# display.net
KiCad netlist of a schematic drawn in EAGLE
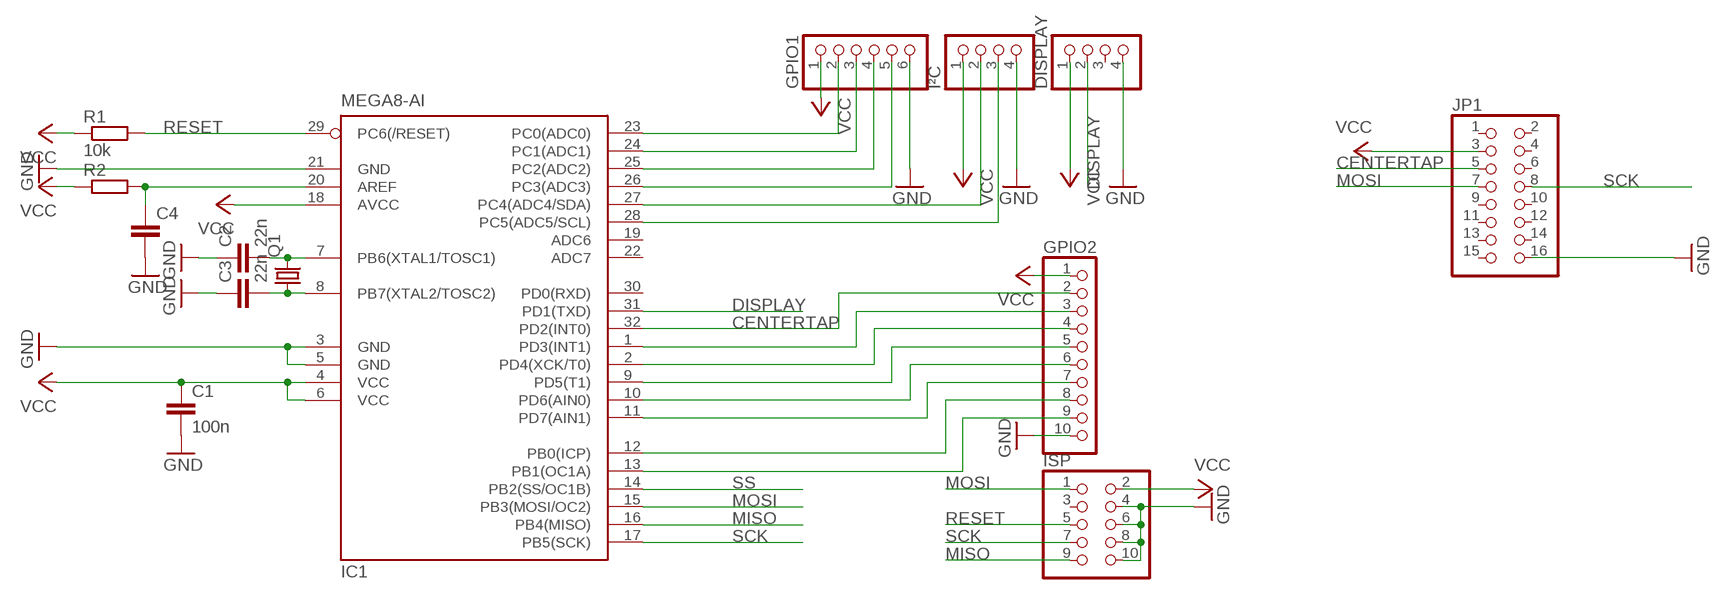
[diagram p0: schematic, sheet 1]

(export (version "E")
  (design (tool "Eeschema 10.0.6"))
  (components
    (comp (ref "C1")
      (value "100n")
      (footprint "eagle-import:C0805")
      (libsource (lib "eagle-import") (part "C-EUC0805"))
    )
    (comp (ref "C2")
      (value "22n")
      (footprint "eagle-import:C0805")
      (libsource (lib "eagle-import") (part "C-EUC0805"))
    )
    (comp (ref "C3")
      (value "22n")
      (footprint "eagle-import:C0805")
      (libsource (lib "eagle-import") (part "C-EUC0805"))
    )
    (comp (ref "C4")
      (value "C-EUC0805")
      (footprint "eagle-import:C0805")
      (libsource (lib "eagle-import") (part "C-EUC0805"))
    )
    (comp (ref "DISPLAY")
      (value "PINHD-1X4")
      (footprint "eagle-import:1X04")
      (libsource (lib "eagle-import") (part "PINHD-1X4"))
    )
    (comp (ref "GPIO1")
      (value "PINHD-1X6")
      (footprint "eagle-import:1X06")
      (libsource (lib "eagle-import") (part "PINHD-1X6"))
    )
    (comp (ref "GPIO2")
      (value "PINHD-1X10")
      (footprint "eagle-import:1X10")
      (libsource (lib "eagle-import") (part "PINHD-1X10"))
    )
    (comp (ref "IC1")
      (value "MEGA8-AI")
      (footprint "eagle-import:TQFP32-08")
      (fields (field (name "MPN") "ATMEGA8-16AU"))
      (libsource (lib "eagle-import") (part "MEGA8-AI"))
    )
    (comp (ref "ISP")
      (value "PINHD-2X5")
      (footprint "eagle-import:2X05")
      (libsource (lib "eagle-import") (part "PINHD-2X5"))
    )
    (comp (ref "I²C")
      (value "PINHD-1X4")
      (footprint "eagle-import:1X04")
      (libsource (lib "eagle-import") (part "PINHD-1X4"))
    )
    (comp (ref "JP1")
      (value "PINHD-2X8")
      (footprint "eagle-import:2X08")
      (libsource (lib "eagle-import") (part "PINHD-2X8"))
    )
    (comp (ref "Q1")
      (value "CRYSTALSM49")
      (footprint "eagle-import:SM49")
      (libsource (lib "eagle-import") (part "CRYSTALSM49"))
    )
    (comp (ref "R1")
      (value "10k")
      (footprint "eagle-import:R0805")
      (libsource (lib "eagle-import") (part "R-EU_R0805"))
    )
    (comp (ref "R2")
      (value "R-EU_R0805")
      (footprint "eagle-import:R0805")
      (libsource (lib "eagle-import") (part "R-EU_R0805"))
    )
  )
  (nets
    (net (code "1") (name "/CENTERTAP") (class "Default")
      (node (ref "GPIO2") (pin "2") (pinfunction "2_2") (pintype "passive"))
      (node (ref "IC1") (pin "32") (pinfunction "PD2(INT0)_32") (pintype "bidirectional"))
      (node (ref "JP1") (pin "5") (pinfunction "5_5") (pintype "passive"))
    )
    (net (code "2") (name "/DISPLAY") (class "Default")
      (node (ref "DISPLAY") (pin "2") (pinfunction "2_2") (pintype "passive"))
      (node (ref "IC1") (pin "31") (pinfunction "PD1(TXD)_31") (pintype "bidirectional"))
    )
    (net (code "3") (name "/MISO") (class "Default")
      (node (ref "IC1") (pin "16") (pinfunction "PB4(MISO)_16") (pintype "bidirectional"))
      (node (ref "ISP") (pin "9") (pinfunction "9_9") (pintype "passive"))
    )
    (net (code "4") (name "/MOSI") (class "Default")
      (node (ref "IC1") (pin "15") (pinfunction "PB3(MOSI/OC2)_15") (pintype "bidirectional"))
      (node (ref "ISP") (pin "1") (pinfunction "1_1") (pintype "passive"))
      (node (ref "JP1") (pin "7") (pinfunction "7_7") (pintype "passive"))
    )
    (net (code "5") (name "/RESET") (class "Default")
      (node (ref "IC1") (pin "29") (pinfunction "PC6(/RESET)_29") (pintype "bidirectional"))
      (node (ref "ISP") (pin "5") (pinfunction "5_5") (pintype "passive"))
      (node (ref "R1") (pin "2") (pinfunction "2_2") (pintype "passive"))
    )
    (net (code "6") (name "/SCK") (class "Default")
      (node (ref "IC1") (pin "17") (pinfunction "PB5(SCK)_17") (pintype "bidirectional"))
      (node (ref "ISP") (pin "7") (pinfunction "7_7") (pintype "passive"))
      (node (ref "JP1") (pin "8") (pinfunction "8_8") (pintype "passive"))
    )
    (net (code "7") (name "/SS") (class "Default")
      (node (ref "IC1") (pin "14") (pinfunction "PB2(SS/OC1B)_14") (pintype "bidirectional"))
    )
    (net (code "8") (name "GND") (class "Default")
      (node (ref "C1") (pin "2") (pinfunction "2_2") (pintype "passive"))
      (node (ref "C2") (pin "1") (pinfunction "1_1") (pintype "passive"))
      (node (ref "C3") (pin "1") (pinfunction "1_1") (pintype "passive"))
      (node (ref "C4") (pin "2") (pinfunction "2_2") (pintype "passive"))
      (node (ref "DISPLAY") (pin "4") (pinfunction "4_4") (pintype "passive"))
      (node (ref "GPIO1") (pin "6") (pinfunction "6_6") (pintype "passive"))
      (node (ref "GPIO2") (pin "10") (pinfunction "10_10") (pintype "passive"))
      (node (ref "IC1") (pin "21") (pinfunction "GND_21") (pintype "power_in"))
      (node (ref "IC1") (pin "3") (pinfunction "GND_3") (pintype "power_in"))
      (node (ref "IC1") (pin "5") (pinfunction "GND_5") (pintype "power_in"))
      (node (ref "ISP") (pin "10") (pinfunction "10_10") (pintype "passive"))
      (node (ref "ISP") (pin "4") (pinfunction "4_4") (pintype "passive"))
      (node (ref "ISP") (pin "6") (pinfunction "6_6") (pintype "passive"))
      (node (ref "ISP") (pin "8") (pinfunction "8_8") (pintype "passive"))
      (node (ref "I²C") (pin "4") (pinfunction "4_4") (pintype "passive"))
      (node (ref "JP1") (pin "16") (pinfunction "16_16") (pintype "passive"))
    )
    (net (code "9") (name "Net-(IC1-AREF)") (class "Default")
      (node (ref "C4") (pin "1") (pinfunction "1_1") (pintype "passive"))
      (node (ref "IC1") (pin "20") (pinfunction "AREF_20") (pintype "passive"))
      (node (ref "R2") (pin "2") (pinfunction "2_2") (pintype "passive"))
    )
    (net (code "10") (name "Net-(IC1-PB0(ICP))") (class "Default")
      (node (ref "GPIO2") (pin "8") (pinfunction "8_8") (pintype "passive"))
      (node (ref "IC1") (pin "12") (pinfunction "PB0(ICP)_12") (pintype "bidirectional"))
    )
    (net (code "11") (name "Net-(IC1-PB1(OC1A))") (class "Default")
      (node (ref "GPIO2") (pin "9") (pinfunction "9_9") (pintype "passive"))
      (node (ref "IC1") (pin "13") (pinfunction "PB1(OC1A)_13") (pintype "bidirectional"))
    )
    (net (code "12") (name "Net-(IC1-PB6(XTAL1{slash}TOSC1))") (class "Default")
      (node (ref "C2") (pin "2") (pinfunction "2_2") (pintype "passive"))
      (node (ref "IC1") (pin "7") (pinfunction "PB6(XTAL1/TOSC1)_7") (pintype "bidirectional"))
      (node (ref "Q1") (pin "2") (pinfunction "2_2") (pintype "passive"))
    )
    (net (code "13") (name "Net-(IC1-PB7(XTAL2{slash}TOSC2))") (class "Default")
      (node (ref "C3") (pin "2") (pinfunction "2_2") (pintype "passive"))
      (node (ref "IC1") (pin "8") (pinfunction "PB7(XTAL2/TOSC2)_8") (pintype "bidirectional"))
      (node (ref "Q1") (pin "1") (pinfunction "1_1") (pintype "passive"))
    )
    (net (code "14") (name "Net-(IC1-PC0(ADC0))") (class "Default")
      (node (ref "GPIO1") (pin "2") (pinfunction "2_2") (pintype "passive"))
      (node (ref "IC1") (pin "23") (pinfunction "PC0(ADC0)_23") (pintype "bidirectional"))
    )
    (net (code "15") (name "Net-(IC1-PC1(ADC1))") (class "Default")
      (node (ref "GPIO1") (pin "3") (pinfunction "3_3") (pintype "passive"))
      (node (ref "IC1") (pin "24") (pinfunction "PC1(ADC1)_24") (pintype "bidirectional"))
    )
    (net (code "16") (name "Net-(IC1-PC2(ADC2))") (class "Default")
      (node (ref "GPIO1") (pin "4") (pinfunction "4_4") (pintype "passive"))
      (node (ref "IC1") (pin "25") (pinfunction "PC2(ADC2)_25") (pintype "bidirectional"))
    )
    (net (code "17") (name "Net-(IC1-PC3(ADC3))") (class "Default")
      (node (ref "GPIO1") (pin "5") (pinfunction "5_5") (pintype "passive"))
      (node (ref "IC1") (pin "26") (pinfunction "PC3(ADC3)_26") (pintype "bidirectional"))
    )
    (net (code "18") (name "Net-(IC1-PC4(ADC4{slash}SDA))") (class "Default")
      (node (ref "IC1") (pin "27") (pinfunction "PC4(ADC4/SDA)_27") (pintype "bidirectional"))
      (node (ref "I²C") (pin "2") (pinfunction "2_2") (pintype "passive"))
    )
    (net (code "19") (name "Net-(IC1-PC5(ADC5{slash}SCL))") (class "Default")
      (node (ref "IC1") (pin "28") (pinfunction "PC5(ADC5/SCL)_28") (pintype "bidirectional"))
      (node (ref "I²C") (pin "3") (pinfunction "3_3") (pintype "passive"))
    )
    (net (code "20") (name "Net-(IC1-PD3(INT1))") (class "Default")
      (node (ref "GPIO2") (pin "3") (pinfunction "3_3") (pintype "passive"))
      (node (ref "IC1") (pin "1") (pinfunction "PD3(INT1)_1") (pintype "bidirectional"))
    )
    (net (code "21") (name "Net-(IC1-PD4(XCK{slash}T0))") (class "Default")
      (node (ref "GPIO2") (pin "4") (pinfunction "4_4") (pintype "passive"))
      (node (ref "IC1") (pin "2") (pinfunction "PD4(XCK/T0)_2") (pintype "bidirectional"))
    )
    (net (code "22") (name "Net-(IC1-PD5(T1))") (class "Default")
      (node (ref "GPIO2") (pin "5") (pinfunction "5_5") (pintype "passive"))
      (node (ref "IC1") (pin "9") (pinfunction "PD5(T1)_9") (pintype "bidirectional"))
    )
    (net (code "23") (name "Net-(IC1-PD6(AIN0))") (class "Default")
      (node (ref "GPIO2") (pin "6") (pinfunction "6_6") (pintype "passive"))
      (node (ref "IC1") (pin "10") (pinfunction "PD6(AIN0)_10") (pintype "bidirectional"))
    )
    (net (code "24") (name "Net-(IC1-PD7(AIN1))") (class "Default")
      (node (ref "GPIO2") (pin "7") (pinfunction "7_7") (pintype "passive"))
      (node (ref "IC1") (pin "11") (pinfunction "PD7(AIN1)_11") (pintype "bidirectional"))
    )
    (net (code "25") (name "VCC") (class "Default")
      (node (ref "C1") (pin "1") (pinfunction "1_1") (pintype "passive"))
      (node (ref "DISPLAY") (pin "1") (pinfunction "1_1") (pintype "passive"))
      (node (ref "GPIO1") (pin "1") (pinfunction "1_1") (pintype "passive"))
      (node (ref "GPIO2") (pin "1") (pinfunction "1_1") (pintype "passive"))
      (node (ref "IC1") (pin "18") (pinfunction "AVCC_18") (pintype "power_in"))
      (node (ref "IC1") (pin "4") (pinfunction "VCC_4") (pintype "power_in"))
      (node (ref "IC1") (pin "6") (pinfunction "VCC_6") (pintype "power_in"))
      (node (ref "ISP") (pin "2") (pinfunction "2_2") (pintype "passive"))
      (node (ref "I²C") (pin "1") (pinfunction "1_1") (pintype "passive"))
      (node (ref "JP1") (pin "3") (pinfunction "3_3") (pintype "passive"))
      (node (ref "R1") (pin "1") (pinfunction "1_1") (pintype "passive"))
      (node (ref "R2") (pin "1") (pinfunction "1_1") (pintype "passive"))
    )
    (net (code "26") (name "unconnected-(DISPLAY-Pad3)") (class "Default")
      (node (ref "DISPLAY") (pin "3") (pinfunction "3_3") (pintype "passive"))
    )
    (net (code "27") (name "unconnected-(IC1-ADC6-Pad19)") (class "Default")
      (node (ref "IC1") (pin "19") (pinfunction "ADC6_19") (pintype "bidirectional"))
    )
    (net (code "28") (name "unconnected-(IC1-ADC7-Pad22)") (class "Default")
      (node (ref "IC1") (pin "22") (pinfunction "ADC7_22") (pintype "bidirectional"))
    )
    (net (code "29") (name "unconnected-(IC1-PD0(RXD)-Pad30)") (class "Default")
      (node (ref "IC1") (pin "30") (pinfunction "PD0(RXD)_30") (pintype "bidirectional"))
    )
    (net (code "30") (name "unconnected-(ISP-Pad3)") (class "Default")
      (node (ref "ISP") (pin "3") (pinfunction "3_3") (pintype "passive"))
    )
    (net (code "31") (name "unconnected-(JP1-Pad1)") (class "Default")
      (node (ref "JP1") (pin "1") (pinfunction "1_1") (pintype "passive"))
    )
    (net (code "32") (name "unconnected-(JP1-Pad2)") (class "Default")
      (node (ref "JP1") (pin "2") (pinfunction "2_2") (pintype "passive"))
    )
    (net (code "33") (name "unconnected-(JP1-Pad4)") (class "Default")
      (node (ref "JP1") (pin "4") (pinfunction "4_4") (pintype "passive"))
    )
    (net (code "34") (name "unconnected-(JP1-Pad6)") (class "Default")
      (node (ref "JP1") (pin "6") (pinfunction "6_6") (pintype "passive"))
    )
    (net (code "35") (name "unconnected-(JP1-Pad9)") (class "Default")
      (node (ref "JP1") (pin "9") (pinfunction "9_9") (pintype "passive"))
    )
    (net (code "36") (name "unconnected-(JP1-Pad10)") (class "Default")
      (node (ref "JP1") (pin "10") (pinfunction "10_10") (pintype "passive"))
    )
    (net (code "37") (name "unconnected-(JP1-Pad11)") (class "Default")
      (node (ref "JP1") (pin "11") (pinfunction "11_11") (pintype "passive"))
    )
    (net (code "38") (name "unconnected-(JP1-Pad12)") (class "Default")
      (node (ref "JP1") (pin "12") (pinfunction "12_12") (pintype "passive"))
    )
    (net (code "39") (name "unconnected-(JP1-Pad13)") (class "Default")
      (node (ref "JP1") (pin "13") (pinfunction "13_13") (pintype "passive"))
    )
    (net (code "40") (name "unconnected-(JP1-Pad14)") (class "Default")
      (node (ref "JP1") (pin "14") (pinfunction "14_14") (pintype "passive"))
    )
    (net (code "41") (name "unconnected-(JP1-Pad15)") (class "Default")
      (node (ref "JP1") (pin "15") (pinfunction "15_15") (pintype "passive"))
    )
  )
)
